# ESP32.net
KiCad netlist of a schematic drawn in Altium Designer
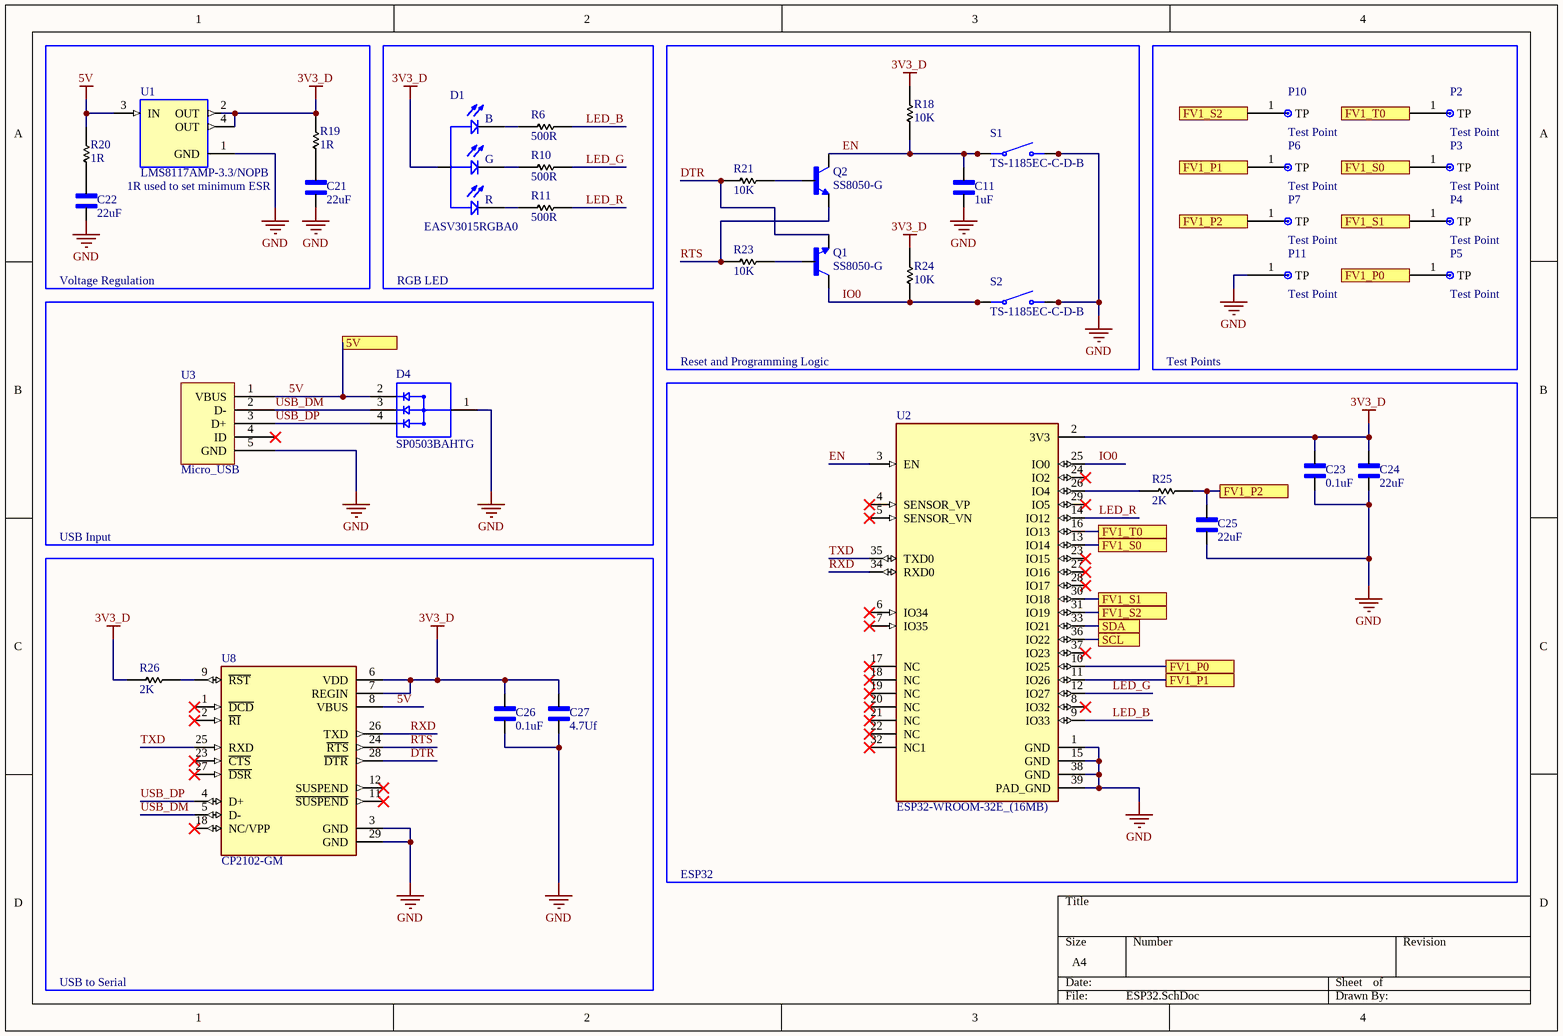
[diagram p0: ESP32.SchDoc]

(export (version "E")
  (design (tool "Eeschema 10.0.6"))
  (components
    (comp (ref "C11")
      (value "1uF")
      (footprint "CHIP_0603")
      (description "Generic 0603 Ceramic Capacitor")
      (fields (field (name "MP") "AC0402FR-071ML") (field (name "MF") "Yageo"))
      (libsource (lib "Guitar_Multi_Effect_lib") (part "0603 Ceramic Capacitor"))
    )
    (comp (ref "C21")
      (value "22uF")
      (footprint "CHIP_0603")
      (description "Generic 0603 Ceramic Capacitor")
      (fields (field (name "MP") "AC0402FR-071ML") (field (name "MF") "Yageo"))
      (libsource (lib "Guitar_Multi_Effect_lib") (part "0603 Ceramic Capacitor"))
    )
    (comp (ref "C22")
      (value "22uF")
      (footprint "CHIP_0603")
      (description "Generic 0603 Ceramic Capacitor")
      (fields (field (name "MP") "AC0402FR-071ML") (field (name "MF") "Yageo"))
      (libsource (lib "Guitar_Multi_Effect_lib") (part "0603 Ceramic Capacitor"))
    )
    (comp (ref "C23")
      (value "0.1uF")
      (footprint "CHIP_0603")
      (description "Generic 0603 Ceramic Capacitor")
      (fields (field (name "MP") "AC0402FR-071ML") (field (name "MF") "Yageo"))
      (libsource (lib "Guitar_Multi_Effect_lib") (part "0603 Ceramic Capacitor"))
    )
    (comp (ref "C24")
      (value "22uF")
      (footprint "CHIP_0603")
      (description "Generic 0603 Ceramic Capacitor")
      (fields (field (name "MP") "AC0402FR-071ML") (field (name "MF") "Yageo"))
      (libsource (lib "Guitar_Multi_Effect_lib") (part "0603 Ceramic Capacitor"))
    )
    (comp (ref "C25")
      (value "22uF")
      (footprint "CHIP_0603")
      (description "Generic 0603 Ceramic Capacitor")
      (fields (field (name "MP") "AC0402FR-071ML") (field (name "MF") "Yageo"))
      (libsource (lib "Guitar_Multi_Effect_lib") (part "0603 Ceramic Capacitor"))
    )
    (comp (ref "C26")
      (value "0.1uF")
      (footprint "CHIP_0603")
      (description "Generic 0603 Ceramic Capacitor")
      (fields (field (name "MP") "AC0402FR-071ML") (field (name "MF") "Yageo"))
      (libsource (lib "Guitar_Multi_Effect_lib") (part "0603 Ceramic Capacitor"))
    )
    (comp (ref "C27")
      (value "4.7Uf")
      (footprint "CHIP_0603")
      (description "Generic 0603 Ceramic Capacitor")
      (fields (field (name "MP") "AC0402FR-071ML") (field (name "MF") "Yageo"))
      (libsource (lib "Guitar_Multi_Effect_lib") (part "0603 Ceramic Capacitor"))
    )
    (comp (ref "D1")
      (value "EASV3015RGBA0")
      (footprint "Guitar_Multi_Effect_lib:LED_EASV3015RGBA0")
      (fields (field (name "MF") "Everlight Electronics"))
      (libsource (lib "Guitar_Multi_Effect_lib") (part "EASV3015RGBA0"))
    )
    (comp (ref "D4")
      (value "SP0503BAHTG")
      (footprint "Guitar_Multi_Effect_lib:SP0503BAHTG")
      (description "8.5V Clamp Ipp Tvs Diode Surface Mount SOT-143-4")
      (fields (field (name "MF") "Littelfuse Inc.") (field (name "DIGI-KEY_PART_NUMBER") "F2715CT-ND"))
      (libsource (lib "Guitar_Multi_Effect_lib") (part "SP0503BAHTG"))
    )
    (comp (ref "P2")
      (value "Test Point")
      (footprint "1 Solder Pad")
      (libsource (lib "Guitar_Multi_Effect_lib") (part "Single Test Point"))
    )
    (comp (ref "P3")
      (value "Test Point")
      (footprint "1 Solder Pad")
      (libsource (lib "Guitar_Multi_Effect_lib") (part "Single Test Point"))
    )
    (comp (ref "P4")
      (value "Test Point")
      (footprint "1 Solder Pad")
      (libsource (lib "Guitar_Multi_Effect_lib") (part "Single Test Point"))
    )
    (comp (ref "P5")
      (value "Test Point")
      (footprint "1 Solder Pad")
      (libsource (lib "Guitar_Multi_Effect_lib") (part "Single Test Point"))
    )
    (comp (ref "P6")
      (value "Test Point")
      (footprint "1 Solder Pad")
      (libsource (lib "Guitar_Multi_Effect_lib") (part "Single Test Point"))
    )
    (comp (ref "P7")
      (value "Test Point")
      (footprint "1 Solder Pad")
      (libsource (lib "Guitar_Multi_Effect_lib") (part "Single Test Point"))
    )
    (comp (ref "P10")
      (value "Test Point")
      (footprint "1 Solder Pad")
      (libsource (lib "Guitar_Multi_Effect_lib") (part "Single Test Point"))
    )
    (comp (ref "P11")
      (value "Test Point")
      (footprint "1 Solder Pad")
      (libsource (lib "Guitar_Multi_Effect_lib") (part "Single Test Point"))
    )
    (comp (ref "Q1")
      (value "SS8050-G")
      (footprint "SS8050-G")
      (description "NPN TRANSISTOR 1.5A 40V SOT-23 R")
      (libsource (lib "Guitar_Multi_Effect_lib") (part "SS8050-G"))
    )
    (comp (ref "Q2")
      (value "SS8050-G")
      (footprint "SS8050-G")
      (description "NPN TRANSISTOR 1.5A 40V SOT-23 R")
      (libsource (lib "") (part "SS8050-G_1"))
    )
    (comp (ref "R6")
      (value "500R")
      (footprint "CHIP_R_0603")
      (description "Generic 0603 Resistor")
      (libsource (lib "Guitar_Multi_Effect_lib") (part "0603 Generic Resistor"))
    )
    (comp (ref "R10")
      (value "500R")
      (footprint "CHIP_R_0603")
      (description "Generic 0603 Resistor")
      (libsource (lib "Guitar_Multi_Effect_lib") (part "0603 Generic Resistor"))
    )
    (comp (ref "R11")
      (value "500R")
      (footprint "CHIP_R_0603")
      (description "Generic 0603 Resistor")
      (libsource (lib "Guitar_Multi_Effect_lib") (part "0603 Generic Resistor"))
    )
    (comp (ref "R18")
      (value "10K")
      (footprint "CHIP_R_0603")
      (description "Generic 0603 Resistor")
      (libsource (lib "Guitar_Multi_Effect_lib") (part "0603 Generic Resistor"))
    )
    (comp (ref "R19")
      (value "1R")
      (footprint "CHIP_R_0603")
      (description "Generic 0603 Resistor")
      (libsource (lib "Guitar_Multi_Effect_lib") (part "0603 Generic Resistor"))
    )
    (comp (ref "R20")
      (value "1R")
      (footprint "CHIP_R_0603")
      (description "Generic 0603 Resistor")
      (libsource (lib "Guitar_Multi_Effect_lib") (part "0603 Generic Resistor"))
    )
    (comp (ref "R21")
      (value "10K")
      (footprint "CHIP_R_0603")
      (description "Generic 0603 Resistor")
      (libsource (lib "Guitar_Multi_Effect_lib") (part "0603 Generic Resistor"))
    )
    (comp (ref "R23")
      (value "10K")
      (footprint "CHIP_R_0603")
      (description "Generic 0603 Resistor")
      (libsource (lib "Guitar_Multi_Effect_lib") (part "0603 Generic Resistor"))
    )
    (comp (ref "R24")
      (value "10K")
      (footprint "CHIP_R_0603")
      (description "Generic 0603 Resistor")
      (libsource (lib "Guitar_Multi_Effect_lib") (part "0603 Generic Resistor"))
    )
    (comp (ref "R25")
      (value "2K")
      (footprint "CHIP_R_0603")
      (description "Generic 0603 Resistor")
      (libsource (lib "Guitar_Multi_Effect_lib") (part "0603 Generic Resistor"))
    )
    (comp (ref "R26")
      (value "2K")
      (footprint "CHIP_R_0603")
      (description "Generic 0603 Resistor")
      (libsource (lib "Guitar_Multi_Effect_lib") (part "0603 Generic Resistor"))
    )
    (comp (ref "S1")
      (value "TS-1185EC-C-D-B")
      (footprint "TS-1185EC-C-D-B")
      (description "SMD Tactile Switche - 3mm 2mm 50mA 3.65mm SPST 12V")
      (libsource (lib "Guitar_Multi_Effect_lib") (part "TS-1185EC-C-D-B"))
    )
    (comp (ref "S2")
      (value "TS-1185EC-C-D-B")
      (footprint "TS-1185EC-C-D-B")
      (description "SMD Tactile Switche - 3mm 2mm 50mA 3.65mm SPST 12V")
      (libsource (lib "Guitar_Multi_Effect_lib") (part "TS-1185EC-C-D-B"))
    )
    (comp (ref "U1")
      (value "LMS8117AMP-3.3/NOPB")
      (footprint "Guitar_Multi_Effect_lib:SOT230P700X180-4N")
      (description "Fixed 3.3V LDO 1A 15V input SOT-223   Cap ESR between 0.5-5R, 10uF minimum")
      (fields (field (name "MF") "Texas Instruments"))
      (libsource (lib "Guitar_Multi_Effect_lib") (part "LMS8117AMP-3.3/NOPB"))
    )
    (comp (ref "U2")
      (value "ESP32-WROOM-32E_(16MB)")
      (footprint "MODULE_ESP32-WROOM-32E")
      (fields (field (name "MP") "ESP32-WROOM-32E (16MB)") (field (name "MF") "Espressif Systems"))
      (libsource (lib "Guitar_Multi_Effect_lib") (part "ESP32-WROOM-32E_(16MB)"))
    )
    (comp (ref "U3")
      (value "Micro_USB")
      (footprint "U254-051T-4BH83-F1S")
      (description "XKB Connectivity U254-051T-4BH83-F1S")
      (libsource (lib "Guitar_Multi_Effect_lib") (part "Micro_USB"))
    )
    (comp (ref "U8")
      (value "CP2102-GM")
      (footprint "QFN50P500X500X100-29N")
      (description "USB Bridge, USB to UART USB 2.0 UART Interface 28-QFN _5x5_")
      (fields (field (name "MF") "Silicon Labs"))
      (libsource (lib "Guitar_Multi_Effect_lib") (part "CP2102-GM"))
    )
  )
  (nets
    (net (code "1") (name "/DTR") (class "Default")
      (node (ref "Q1") (pin "2") (pinfunction "E_2") (pintype "passive"))
      (node (ref "R21") (pin "2") (pinfunction "2_2") (pintype "passive"))
      (node (ref "U8") (pin "28") (pinfunction "~{DTR}_28") (pintype "output"))
    )
    (net (code "2") (name "/EN") (class "Default")
      (node (ref "C11") (pin "1") (pinfunction "1_1") (pintype "passive"))
      (node (ref "Q2") (pin "3") (pinfunction "C_3") (pintype "passive"))
      (node (ref "R18") (pin "2") (pinfunction "2_2") (pintype "passive"))
      (node (ref "S1") (pin "1") (pinfunction "COM_1") (pintype "passive"))
      (node (ref "S1") (pin "2") (pinfunction "COM_2") (pintype "passive"))
      (node (ref "U2") (pin "3") (pinfunction "EN_3") (pintype "input"))
    )
    (net (code "3") (name "/FV1_P0") (class "Default")
      (node (ref "P5") (pin "1") (pinfunction "TP_1") (pintype "passive"))
      (node (ref "U2") (pin "10") (pinfunction "IO25_10") (pintype "bidirectional"))
    )
    (net (code "4") (name "/FV1_P1") (class "Default")
      (node (ref "P6") (pin "1") (pinfunction "TP_1") (pintype "passive"))
      (node (ref "U2") (pin "11") (pinfunction "IO26_11") (pintype "bidirectional"))
    )
    (net (code "5") (name "/FV1_P2") (class "Default")
      (node (ref "C25") (pin "1") (pinfunction "1_1") (pintype "passive"))
      (node (ref "P7") (pin "1") (pinfunction "TP_1") (pintype "passive"))
      (node (ref "R25") (pin "2") (pinfunction "2_2") (pintype "passive"))
    )
    (net (code "6") (name "/FV1_S0") (class "Default")
      (node (ref "P3") (pin "1") (pinfunction "TP_1") (pintype "passive"))
      (node (ref "U2") (pin "13") (pinfunction "IO14_13") (pintype "bidirectional"))
    )
    (net (code "7") (name "/FV1_S1") (class "Default")
      (node (ref "P4") (pin "1") (pinfunction "TP_1") (pintype "passive"))
      (node (ref "U2") (pin "30") (pinfunction "IO18_30") (pintype "bidirectional"))
    )
    (net (code "8") (name "/FV1_S2") (class "Default")
      (node (ref "P10") (pin "1") (pinfunction "TP_1") (pintype "passive"))
      (node (ref "U2") (pin "31") (pinfunction "IO19_31") (pintype "bidirectional"))
    )
    (net (code "9") (name "/FV1_T0") (class "Default")
      (node (ref "P2") (pin "1") (pinfunction "TP_1") (pintype "passive"))
      (node (ref "U2") (pin "16") (pinfunction "IO13_16") (pintype "bidirectional"))
    )
    (net (code "10") (name "/IO0") (class "Default")
      (node (ref "Q1") (pin "3") (pinfunction "C_3") (pintype "passive"))
      (node (ref "R24") (pin "2") (pinfunction "2_2") (pintype "passive"))
      (node (ref "S2") (pin "1") (pinfunction "COM_1") (pintype "passive"))
      (node (ref "S2") (pin "2") (pinfunction "COM_2") (pintype "passive"))
      (node (ref "U2") (pin "25") (pinfunction "IO0_25") (pintype "bidirectional"))
    )
    (net (code "11") (name "/LED_B") (class "Default")
      (node (ref "R6") (pin "1") (pinfunction "1_1") (pintype "passive"))
      (node (ref "U2") (pin "9") (pinfunction "IO33_9") (pintype "bidirectional"))
    )
    (net (code "12") (name "/LED_G") (class "Default")
      (node (ref "R10") (pin "1") (pinfunction "1_1") (pintype "passive"))
      (node (ref "U2") (pin "12") (pinfunction "IO27_12") (pintype "bidirectional"))
    )
    (net (code "13") (name "/LED_R") (class "Default")
      (node (ref "R11") (pin "1") (pinfunction "1_1") (pintype "passive"))
      (node (ref "U2") (pin "14") (pinfunction "IO12_14") (pintype "bidirectional"))
    )
    (net (code "14") (name "/RTS") (class "Default")
      (node (ref "Q2") (pin "2") (pinfunction "E_2") (pintype "passive"))
      (node (ref "R23") (pin "2") (pinfunction "2_2") (pintype "passive"))
      (node (ref "U8") (pin "24") (pinfunction "~{RTS}_24") (pintype "output"))
    )
    (net (code "15") (name "/RXD") (class "Default")
      (node (ref "U2") (pin "34") (pinfunction "RXD0_34") (pintype "bidirectional"))
      (node (ref "U8") (pin "26") (pinfunction "TXD_26") (pintype "output"))
    )
    (net (code "16") (name "/SCL") (class "Default")
      (node (ref "U2") (pin "36") (pinfunction "IO22_36") (pintype "bidirectional"))
    )
    (net (code "17") (name "/SDA") (class "Default")
      (node (ref "U2") (pin "33") (pinfunction "IO21_33") (pintype "bidirectional"))
    )
    (net (code "18") (name "/TXD") (class "Default")
      (node (ref "U2") (pin "35") (pinfunction "TXD0_35") (pintype "bidirectional"))
      (node (ref "U8") (pin "25") (pinfunction "RXD_25") (pintype "input"))
    )
    (net (code "19") (name "/USB_DM") (class "Default")
      (node (ref "D4") (pin "3") (pinfunction "3_3") (pintype "passive"))
      (node (ref "U3") (pin "2") (pinfunction "D-_2") (pintype "passive"))
      (node (ref "U8") (pin "5") (pinfunction "D-_5") (pintype "bidirectional"))
    )
    (net (code "20") (name "/USB_DP") (class "Default")
      (node (ref "D4") (pin "4") (pinfunction "4_4") (pintype "passive"))
      (node (ref "U3") (pin "3") (pinfunction "D+_3") (pintype "passive"))
      (node (ref "U8") (pin "4") (pinfunction "D+_4") (pintype "bidirectional"))
    )
    (net (code "21") (name "3V3_D") (class "Default")
      (node (ref "C23") (pin "1") (pinfunction "1_1") (pintype "passive"))
      (node (ref "C24") (pin "1") (pinfunction "1_1") (pintype "passive"))
      (node (ref "C26") (pin "1") (pinfunction "1_1") (pintype "passive"))
      (node (ref "C27") (pin "1") (pinfunction "1_1") (pintype "passive"))
      (node (ref "D1") (pin "1") (pinfunction "1_1") (pintype "passive"))
      (node (ref "R18") (pin "1") (pinfunction "1_1") (pintype "passive"))
      (node (ref "R19") (pin "1") (pinfunction "1_1") (pintype "passive"))
      (node (ref "R24") (pin "1") (pinfunction "1_1") (pintype "passive"))
      (node (ref "R26") (pin "2") (pinfunction "2_2") (pintype "passive"))
      (node (ref "U1") (pin "2") (pinfunction "OUT_2") (pintype "output"))
      (node (ref "U1") (pin "4") (pinfunction "OUT_4") (pintype "output"))
      (node (ref "U2") (pin "2") (pinfunction "3V3_2") (pintype "power_in"))
      (node (ref "U8") (pin "6") (pinfunction "VDD_6") (pintype "power_in"))
      (node (ref "U8") (pin "7") (pinfunction "REGIN_7") (pintype "power_in"))
    )
    (net (code "22") (name "5V") (class "Default")
      (node (ref "D4") (pin "2") (pinfunction "2_2") (pintype "passive"))
      (node (ref "R20") (pin "1") (pinfunction "1_1") (pintype "passive"))
      (node (ref "U1") (pin "3") (pinfunction "IN_3") (pintype "input"))
      (node (ref "U3") (pin "1") (pinfunction "VBUS_1") (pintype "passive"))
      (node (ref "U8") (pin "8") (pinfunction "VBUS_8") (pintype "power_in"))
    )
    (net (code "23") (name "GND") (class "Default")
      (node (ref "C11") (pin "2") (pinfunction "2_2") (pintype "passive"))
      (node (ref "C21") (pin "2") (pinfunction "2_2") (pintype "passive"))
      (node (ref "C22") (pin "2") (pinfunction "2_2") (pintype "passive"))
      (node (ref "C23") (pin "2") (pinfunction "2_2") (pintype "passive"))
      (node (ref "C24") (pin "2") (pinfunction "2_2") (pintype "passive"))
      (node (ref "C25") (pin "2") (pinfunction "2_2") (pintype "passive"))
      (node (ref "C26") (pin "2") (pinfunction "2_2") (pintype "passive"))
      (node (ref "C27") (pin "2") (pinfunction "2_2") (pintype "passive"))
      (node (ref "D4") (pin "1") (pinfunction "1_1") (pintype "passive"))
      (node (ref "P11") (pin "1") (pinfunction "TP_1") (pintype "passive"))
      (node (ref "S1") (pin "3") (pinfunction "NO_3") (pintype "passive"))
      (node (ref "S1") (pin "4") (pinfunction "NO_4") (pintype "passive"))
      (node (ref "S2") (pin "3") (pinfunction "NO_3") (pintype "passive"))
      (node (ref "S2") (pin "4") (pinfunction "NO_4") (pintype "passive"))
      (node (ref "U1") (pin "1") (pinfunction "GND_1") (pintype "power_in"))
      (node (ref "U2") (pin "1") (pinfunction "GND_1") (pintype "power_in"))
      (node (ref "U2") (pin "15") (pinfunction "GND_15") (pintype "power_in"))
      (node (ref "U2") (pin "38") (pinfunction "GND_38") (pintype "power_in"))
      (node (ref "U2") (pin "39") (pinfunction "PAD_GND_39") (pintype "power_in"))
      (node (ref "U3") (pin "5") (pinfunction "GND_5") (pintype "passive"))
      (node (ref "U8") (pin "29") (pinfunction "GND_29") (pintype "power_in"))
      (node (ref "U8") (pin "3") (pinfunction "GND_3") (pintype "power_in"))
    )
    (net (code "24") (name "Net-(C21-Pad1)") (class "Default")
      (node (ref "C21") (pin "1") (pinfunction "1_1") (pintype "passive"))
      (node (ref "R19") (pin "2") (pinfunction "2_2") (pintype "passive"))
    )
    (net (code "25") (name "Net-(C22-Pad1)") (class "Default")
      (node (ref "C22") (pin "1") (pinfunction "1_1") (pintype "passive"))
      (node (ref "R20") (pin "2") (pinfunction "2_2") (pintype "passive"))
    )
    (net (code "26") (name "Net-(D1-Pad2)") (class "Default")
      (node (ref "D1") (pin "2") (pinfunction "2_2") (pintype "passive"))
      (node (ref "R6") (pin "2") (pinfunction "2_2") (pintype "passive"))
    )
    (net (code "27") (name "Net-(D1-Pad3)") (class "Default")
      (node (ref "D1") (pin "3") (pinfunction "3_3") (pintype "passive"))
      (node (ref "R10") (pin "2") (pinfunction "2_2") (pintype "passive"))
    )
    (net (code "28") (name "Net-(D1-Pad4)") (class "Default")
      (node (ref "D1") (pin "4") (pinfunction "4_4") (pintype "passive"))
      (node (ref "R11") (pin "2") (pinfunction "2_2") (pintype "passive"))
    )
    (net (code "29") (name "Net-(Q1-B)") (class "Default")
      (node (ref "Q1") (pin "1") (pinfunction "B_1") (pintype "passive"))
      (node (ref "R23") (pin "1") (pinfunction "1_1") (pintype "passive"))
    )
    (net (code "30") (name "Net-(Q2-B)") (class "Default")
      (node (ref "Q2") (pin "1") (pinfunction "B_1") (pintype "passive"))
      (node (ref "R21") (pin "1") (pinfunction "1_1") (pintype "passive"))
    )
    (net (code "31") (name "Net-(U2-IO4)") (class "Default")
      (node (ref "R25") (pin "1") (pinfunction "1_1") (pintype "passive"))
      (node (ref "U2") (pin "26") (pinfunction "IO4_26") (pintype "bidirectional"))
    )
    (net (code "32") (name "Net-(U8-~{RST})") (class "Default")
      (node (ref "R26") (pin "1") (pinfunction "1_1") (pintype "passive"))
      (node (ref "U8") (pin "9") (pinfunction "~{RST}_9") (pintype "bidirectional"))
    )
    (net (code "33") (name "unconnected-(U2-IO2-Pad24)") (class "Default")
      (node (ref "U2") (pin "24") (pinfunction "IO2_24") (pintype "bidirectional+no_connect"))
    )
    (net (code "34") (name "unconnected-(U2-IO5-Pad29)") (class "Default")
      (node (ref "U2") (pin "29") (pinfunction "IO5_29") (pintype "bidirectional+no_connect"))
    )
    (net (code "35") (name "unconnected-(U2-IO15-Pad23)") (class "Default")
      (node (ref "U2") (pin "23") (pinfunction "IO15_23") (pintype "bidirectional+no_connect"))
    )
    (net (code "36") (name "unconnected-(U2-IO16-Pad27)") (class "Default")
      (node (ref "U2") (pin "27") (pinfunction "IO16_27") (pintype "bidirectional+no_connect"))
    )
    (net (code "37") (name "unconnected-(U2-IO17-Pad28)") (class "Default")
      (node (ref "U2") (pin "28") (pinfunction "IO17_28") (pintype "bidirectional+no_connect"))
    )
    (net (code "38") (name "unconnected-(U2-IO23-Pad37)") (class "Default")
      (node (ref "U2") (pin "37") (pinfunction "IO23_37") (pintype "bidirectional+no_connect"))
    )
    (net (code "39") (name "unconnected-(U2-IO32-Pad8)") (class "Default")
      (node (ref "U2") (pin "8") (pinfunction "IO32_8") (pintype "bidirectional+no_connect"))
    )
    (net (code "40") (name "unconnected-(U2-IO34-Pad6)") (class "Default")
      (node (ref "U2") (pin "6") (pinfunction "IO34_6") (pintype "input+no_connect"))
    )
    (net (code "41") (name "unconnected-(U2-IO35-Pad7)") (class "Default")
      (node (ref "U2") (pin "7") (pinfunction "IO35_7") (pintype "input+no_connect"))
    )
    (net (code "42") (name "unconnected-(U2-NC-Pad17)") (class "Default")
      (node (ref "U2") (pin "17") (pinfunction "NC_17") (pintype "passive+no_connect"))
    )
    (net (code "43") (name "unconnected-(U2-NC-Pad18)") (class "Default")
      (node (ref "U2") (pin "18") (pinfunction "NC_18") (pintype "passive+no_connect"))
    )
    (net (code "44") (name "unconnected-(U2-NC-Pad19)") (class "Default")
      (node (ref "U2") (pin "19") (pinfunction "NC_19") (pintype "passive+no_connect"))
    )
    (net (code "45") (name "unconnected-(U2-NC-Pad20)") (class "Default")
      (node (ref "U2") (pin "20") (pinfunction "NC_20") (pintype "passive+no_connect"))
    )
    (net (code "46") (name "unconnected-(U2-NC-Pad21)") (class "Default")
      (node (ref "U2") (pin "21") (pinfunction "NC_21") (pintype "passive+no_connect"))
    )
    (net (code "47") (name "unconnected-(U2-NC-Pad22)") (class "Default")
      (node (ref "U2") (pin "22") (pinfunction "NC_22") (pintype "passive+no_connect"))
    )
    (net (code "48") (name "unconnected-(U2-NC1-Pad32)") (class "Default")
      (node (ref "U2") (pin "32") (pinfunction "NC1_32") (pintype "passive+no_connect"))
    )
    (net (code "49") (name "unconnected-(U2-SENSOR_VN-Pad5)") (class "Default")
      (node (ref "U2") (pin "5") (pinfunction "SENSOR_VN_5") (pintype "input+no_connect"))
    )
    (net (code "50") (name "unconnected-(U2-SENSOR_VP-Pad4)") (class "Default")
      (node (ref "U2") (pin "4") (pinfunction "SENSOR_VP_4") (pintype "input+no_connect"))
    )
    (net (code "51") (name "unconnected-(U3-ID-Pad4)") (class "Default")
      (node (ref "U3") (pin "4") (pinfunction "ID_4") (pintype "passive+no_connect"))
    )
    (net (code "52") (name "unconnected-(U8-NC{slash}VPP-Pad18)") (class "Default")
      (node (ref "U8") (pin "18") (pinfunction "NC/VPP_18") (pintype "bidirectional+no_connect"))
    )
    (net (code "53") (name "unconnected-(U8-SUSPEND-Pad12)") (class "Default")
      (node (ref "U8") (pin "12") (pinfunction "SUSPEND_12") (pintype "output+no_connect"))
    )
    (net (code "54") (name "unconnected-(U8-~{CTS}-Pad23)") (class "Default")
      (node (ref "U8") (pin "23") (pinfunction "~{CTS}_23") (pintype "input+no_connect"))
    )
    (net (code "55") (name "unconnected-(U8-~{DCD}-Pad1)") (class "Default")
      (node (ref "U8") (pin "1") (pinfunction "~{DCD}_1") (pintype "input+no_connect"))
    )
    (net (code "56") (name "unconnected-(U8-~{DSR}-Pad27)") (class "Default")
      (node (ref "U8") (pin "27") (pinfunction "~{DSR}_27") (pintype "input+no_connect"))
    )
    (net (code "57") (name "unconnected-(U8-~{RI}-Pad2)") (class "Default")
      (node (ref "U8") (pin "2") (pinfunction "~{RI}_2") (pintype "input+no_connect"))
    )
    (net (code "58") (name "unconnected-(U8-~{SUSPEND}-Pad11)") (class "Default")
      (node (ref "U8") (pin "11") (pinfunction "~{SUSPEND}_11") (pintype "output+no_connect"))
    )
  )
)
